# B5_EM__Z_SOLAR_PANEL.net
KiCad netlist of a schematic drawn in EAGLE
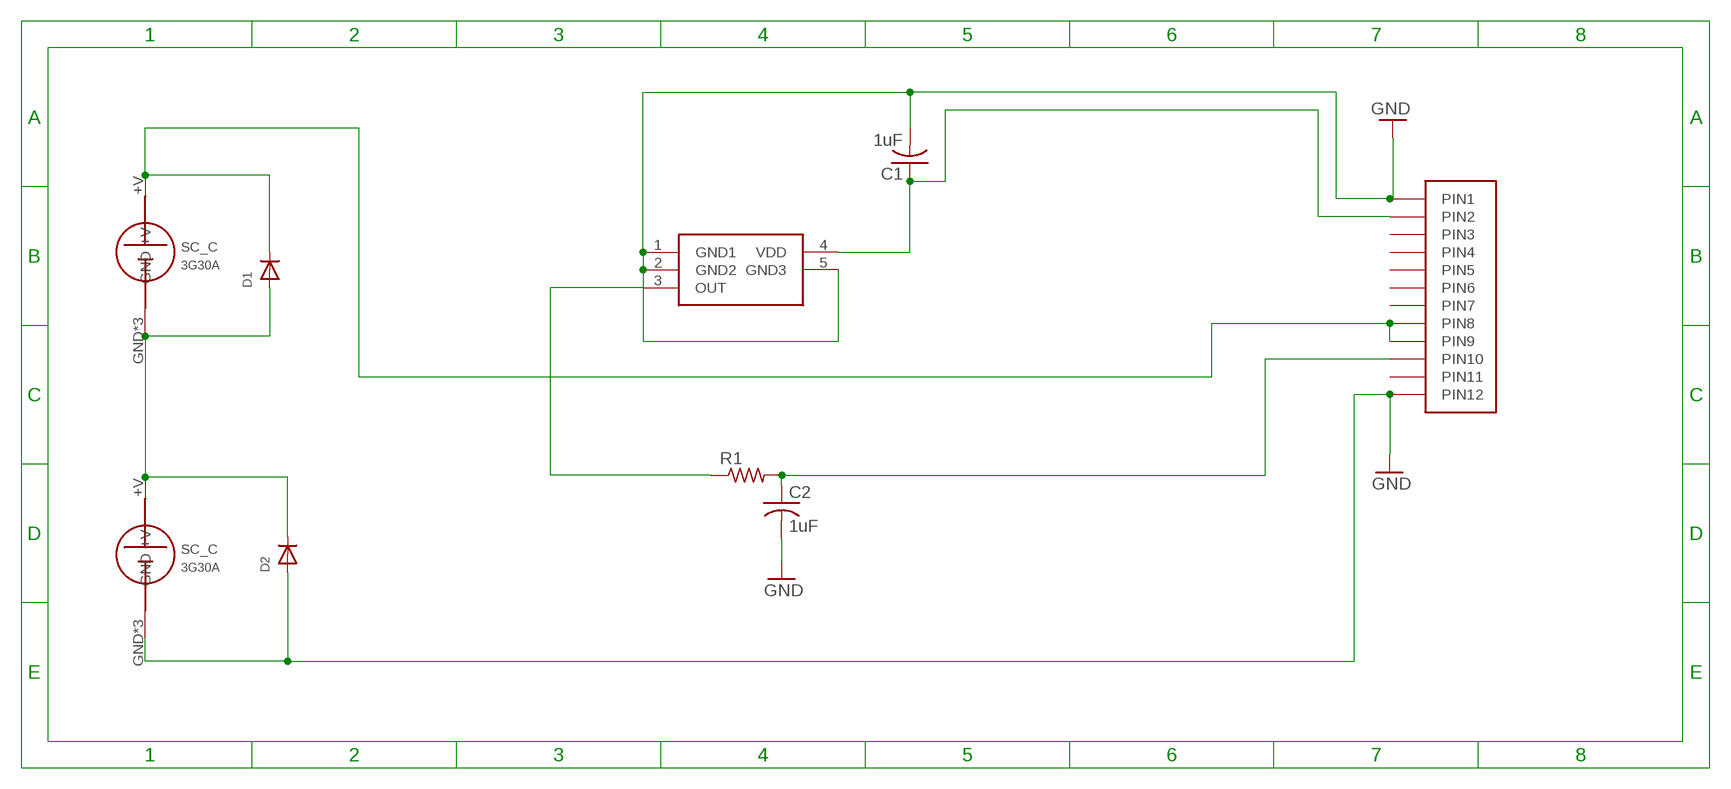
[diagram p0: schematic, sheet 1]

(export (version "E")
  (design (tool "Eeschema 10.0.6"))
  (components
    (comp (ref "C1")
      (value "1uF")
      (footprint "eagle-import:C0805")
      (libsource (lib "eagle-import") (part "C-USC0805"))
    )
    (comp (ref "C2")
      (value "1uF")
      (footprint "eagle-import:C0805")
      (libsource (lib "eagle-import") (part "C-USC0805"))
    )
    (comp (ref "D1")
      (value "DIODE_SOD-123FL")
      (footprint "eagle-import:SOD-123FL")
      (libsource (lib "eagle-import") (part "DIODE_SOD-123FL"))
    )
    (comp (ref "D2")
      (value "DIODE_SOD-123FL")
      (footprint "eagle-import:SOD-123FL")
      (libsource (lib "eagle-import") (part "DIODE_SOD-123FL"))
    )
    (comp (ref "R1")
      (value "R-US_R0402")
      (footprint "eagle-import:R0402")
      (libsource (lib "eagle-import") (part "R-US_R0402"))
    )
    (comp (ref "U$1")
      (value "HEADER12PIN")
      (footprint "eagle-import:HEADER12PIN")
      (libsource (lib "eagle-import") (part "HEADER12PIN"))
    )
    (comp (ref "U$3")
      (value "LMT84DCKT")
      (footprint "eagle-import:SOT65P210X110-5N")
      (fields (field (name "RS_PART_NUMBER") "8115860"))
      (libsource (lib "eagle-import") (part "LMT84DCKT"))
    )
    (comp (ref "U$4")
      (value "SC_C")
      (footprint "eagle-import:SC_C")
      (libsource (lib "eagle-import") (part "SC_C"))
    )
    (comp (ref "U$5")
      (value "SC_C")
      (footprint "eagle-import:SC_C")
      (libsource (lib "eagle-import") (part "SC_C"))
    )
  )
  (nets
    (net (code "1") (name "GND") (class "Default")
      (node (ref "C1") (pin "2") (pinfunction "2_2") (pintype "passive"))
      (node (ref "C2") (pin "2") (pinfunction "2_2") (pintype "passive"))
      (node (ref "D2") (pin "A") (pinfunction "A_A") (pintype "passive"))
      (node (ref "U$1") (pin "P1") (pinfunction "PIN1_P1") (pintype "bidirectional"))
      (node (ref "U$1") (pin "P12") (pinfunction "PIN12_P12") (pintype "bidirectional"))
      (node (ref "U$3") (pin "1") (pinfunction "GND1_1") (pintype "power_in"))
      (node (ref "U$3") (pin "2") (pinfunction "GND2_2") (pintype "power_in"))
      (node (ref "U$3") (pin "5") (pinfunction "GND3_5") (pintype "power_in"))
      (node (ref "U$4") (pin "GND") (pinfunction "GND_GND") (pintype "bidirectional"))
      (node (ref "U$4") (pin "GND1") (pinfunction "GND_GND1") (pintype "bidirectional"))
      (node (ref "U$4") (pin "GND2") (pinfunction "GND_GND2") (pintype "bidirectional"))
    )
    (net (code "2") (name "Net-(D1-PadA)") (class "Default")
      (node (ref "D1") (pin "A") (pinfunction "A_A") (pintype "passive"))
      (node (ref "D2") (pin "C") (pinfunction "C_C") (pintype "passive"))
      (node (ref "U$4") (pin "+V") (pinfunction "+V_+V") (pintype "bidirectional"))
      (node (ref "U$5") (pin "GND") (pinfunction "GND_GND") (pintype "bidirectional"))
      (node (ref "U$5") (pin "GND1") (pinfunction "GND_GND1") (pintype "bidirectional"))
      (node (ref "U$5") (pin "GND2") (pinfunction "GND_GND2") (pintype "bidirectional"))
    )
    (net (code "3") (name "Net-(U$1-PIN2)") (class "Default")
      (node (ref "C1") (pin "1") (pinfunction "1_1") (pintype "passive"))
      (node (ref "U$1") (pin "P2") (pinfunction "PIN2_P2") (pintype "bidirectional"))
      (node (ref "U$3") (pin "4") (pinfunction "VDD_4") (pintype "power_in"))
    )
    (net (code "4") (name "Net-(U$1-PIN8)") (class "Default")
      (node (ref "D1") (pin "C") (pinfunction "C_C") (pintype "passive"))
      (node (ref "U$1") (pin "P8") (pinfunction "PIN8_P8") (pintype "bidirectional"))
      (node (ref "U$1") (pin "P9") (pinfunction "PIN9_P9") (pintype "bidirectional"))
      (node (ref "U$5") (pin "+V") (pinfunction "+V_+V") (pintype "bidirectional"))
    )
    (net (code "5") (name "Net-(U$1-PIN10)") (class "Default")
      (node (ref "C2") (pin "1") (pinfunction "1_1") (pintype "passive"))
      (node (ref "R1") (pin "2") (pinfunction "2_2") (pintype "passive"))
      (node (ref "U$1") (pin "P10") (pinfunction "PIN10_P10") (pintype "bidirectional"))
    )
    (net (code "6") (name "Net-(U$3-OUT)") (class "Default")
      (node (ref "R1") (pin "1") (pinfunction "1_1") (pintype "passive"))
      (node (ref "U$3") (pin "3") (pinfunction "OUT_3") (pintype "output"))
    )
    (net (code "7") (name "unconnected-(U$1-PIN3-PadP3)") (class "Default")
      (node (ref "U$1") (pin "P3") (pinfunction "PIN3_P3") (pintype "bidirectional"))
    )
    (net (code "8") (name "unconnected-(U$1-PIN4-PadP4)") (class "Default")
      (node (ref "U$1") (pin "P4") (pinfunction "PIN4_P4") (pintype "bidirectional"))
    )
    (net (code "9") (name "unconnected-(U$1-PIN5-PadP5)") (class "Default")
      (node (ref "U$1") (pin "P5") (pinfunction "PIN5_P5") (pintype "bidirectional"))
    )
    (net (code "10") (name "unconnected-(U$1-PIN6-PadP6)") (class "Default")
      (node (ref "U$1") (pin "P6") (pinfunction "PIN6_P6") (pintype "bidirectional"))
    )
    (net (code "11") (name "unconnected-(U$1-PIN7-PadP7)") (class "Default")
      (node (ref "U$1") (pin "P7") (pinfunction "PIN7_P7") (pintype "bidirectional"))
    )
    (net (code "12") (name "unconnected-(U$1-PIN11-PadP11)") (class "Default")
      (node (ref "U$1") (pin "P11") (pinfunction "PIN11_P11") (pintype "bidirectional"))
    )
  )
)
